# Strain.net
KiCad netlist of a schematic drawn in Altium Designer
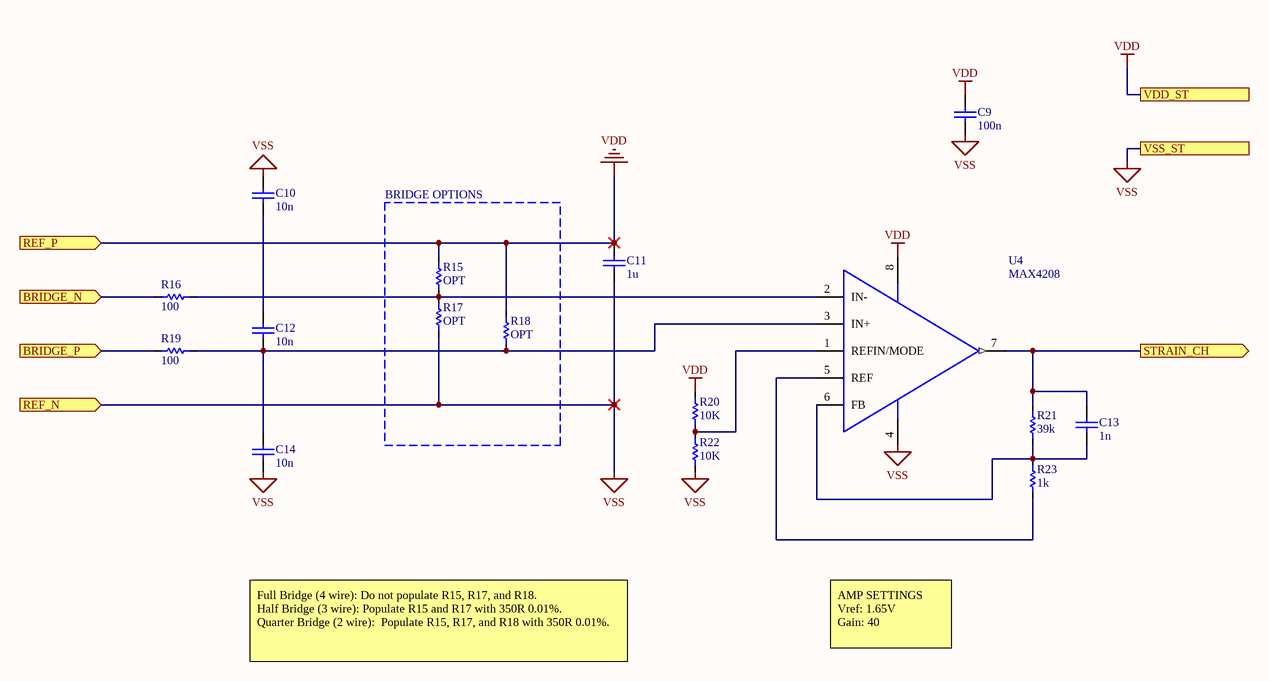
[diagram p0: Strain.SchDoc]

(export (version "E")
  (design (tool "Eeschema 10.0.6"))
  (components
    (comp (ref "C9")
      (value "100n")
      (footprint "CAP_0603_M")
      (description "CAP Cnom Vcap Ptol Dial 0603")
      (fields (field (name "CREATED BY") "JS"))
      (libsource (lib "Passives") (part "CAP_0603"))
    )
    (comp (ref "C10")
      (value "10n")
      (footprint "CAP_0603_M")
      (description "CAP Cnom Vcap Ptol Dial 0603")
      (fields (field (name "CREATED BY") "JS"))
      (libsource (lib "Passives") (part "CAP_0603"))
    )
    (comp (ref "C11")
      (value "1u")
      (footprint "CAP_0603_M")
      (description "CAP Cnom Vcap Ptol Dial 0603")
      (fields (field (name "CREATED BY") "JS"))
      (libsource (lib "Passives") (part "CAP_0603"))
    )
    (comp (ref "C12")
      (value "10n")
      (footprint "CAP_0603_M")
      (description "CAP Cnom Vcap Ptol Dial 0603")
      (fields (field (name "CREATED BY") "JS"))
      (libsource (lib "Passives") (part "CAP_0603"))
    )
    (comp (ref "C13")
      (value "1n")
      (footprint "CAP_0603_M")
      (description "CAP Cnom Vcap Ptol Dial 0603")
      (fields (field (name "CREATED BY") "JS"))
      (libsource (lib "Passives") (part "CAP_0603"))
    )
    (comp (ref "C14")
      (value "10n")
      (footprint "CAP_0603_M")
      (description "CAP Cnom Vcap Ptol Dial 0603")
      (fields (field (name "CREATED BY") "JS"))
      (libsource (lib "Passives") (part "CAP_0603"))
    )
    (comp (ref "R15")
      (value "OPT")
      (footprint "RES_0603_M")
      (description "RES OPT 1/5W 0603")
      (fields (field (name "CREATED BY") "JS"))
      (libsource (lib "Passives") (part "RES_0603"))
    )
    (comp (ref "R16")
      (value "100")
      (footprint "RES_0603_M")
      (description "RES OPT 1/5W 0603")
      (fields (field (name "CREATED BY") "JS"))
      (libsource (lib "Passives") (part "RES_0603"))
    )
    (comp (ref "R17")
      (value "OPT")
      (footprint "RES_0603_M")
      (description "RES OPT 1/5W 0603")
      (fields (field (name "CREATED BY") "JS"))
      (libsource (lib "Passives") (part "RES_0603"))
    )
    (comp (ref "R18")
      (value "OPT")
      (footprint "RES_0603_M")
      (description "RES OPT 1/5W 0603")
      (fields (field (name "CREATED BY") "JS"))
      (libsource (lib "Passives") (part "RES_0603"))
    )
    (comp (ref "R19")
      (value "100")
      (footprint "RES_0603_M")
      (description "RES OPT 1/5W 0603")
      (fields (field (name "CREATED BY") "JS"))
      (libsource (lib "Passives") (part "RES_0603"))
    )
    (comp (ref "R20")
      (value "10K")
      (footprint "RES_0603_M")
      (description "RES OPT 1/5W 0603")
      (fields (field (name "CREATED BY") "JS"))
      (libsource (lib "Passives") (part "RES_0603"))
    )
    (comp (ref "R21")
      (value "39k")
      (footprint "RES_0603_M")
      (description "RES OPT 1/5W 0603")
      (fields (field (name "CREATED BY") "JS"))
      (libsource (lib "Passives") (part "RES_0603"))
    )
    (comp (ref "R22")
      (value "10K")
      (footprint "RES_0603_M")
      (description "RES OPT 1/5W 0603")
      (fields (field (name "CREATED BY") "JS"))
      (libsource (lib "Passives") (part "RES_0603"))
    )
    (comp (ref "R23")
      (value "1k")
      (footprint "RES_0603_M")
      (description "RES OPT 1/5W 0603")
      (fields (field (name "CREATED BY") "JS"))
      (libsource (lib "Passives") (part "RES_0603"))
    )
    (comp (ref "U4")
      (value "MAX4208")
      (footprint "MAX4208_SOP127P600-8N")
      (fields (field (name "MANUFACTURER") "Maxim"))
      (libsource (lib "IC") (part "MAX4208"))
    )
  )
  (nets
    (net (code "1") (name "/BRIDGE_N") (class "Default")
      (node (ref "R16") (pin "1") (pinfunction "1_1") (pintype "passive"))
    )
    (net (code "2") (name "/BRIDGE_P") (class "Default")
      (node (ref "R19") (pin "1") (pinfunction "1_1") (pintype "passive"))
    )
    (net (code "3") (name "/STRAIN_CH") (class "Default")
      (node (ref "C13") (pin "2") (pinfunction "2_2") (pintype "passive"))
      (node (ref "R21") (pin "2") (pinfunction "2_2") (pintype "passive"))
      (node (ref "U4") (pin "7") (pinfunction "VO_7") (pintype "output"))
    )
    (net (code "4") (name "Net-(C10-Pad1)") (class "Default")
      (node (ref "C10") (pin "1") (pinfunction "1_1") (pintype "passive"))
      (node (ref "C12") (pin "2") (pinfunction "2_2") (pintype "passive"))
    )
    (net (code "5") (name "Net-(U4-FB)") (class "Default")
      (node (ref "C13") (pin "1") (pinfunction "1_1") (pintype "passive"))
      (node (ref "R21") (pin "1") (pinfunction "1_1") (pintype "passive"))
      (node (ref "R23") (pin "2") (pinfunction "2_2") (pintype "passive"))
      (node (ref "U4") (pin "6") (pinfunction "FB_6") (pintype "passive"))
    )
    (net (code "6") (name "Net-(U4-IN+)") (class "Default")
      (node (ref "C12") (pin "1") (pinfunction "1_1") (pintype "passive"))
      (node (ref "C14") (pin "2") (pinfunction "2_2") (pintype "passive"))
      (node (ref "R18") (pin "1") (pinfunction "1_1") (pintype "passive"))
      (node (ref "R19") (pin "2") (pinfunction "2_2") (pintype "passive"))
      (node (ref "U4") (pin "3") (pinfunction "IN+_3") (pintype "passive"))
    )
    (net (code "7") (name "Net-(U4-IN-)") (class "Default")
      (node (ref "R15") (pin "1") (pinfunction "1_1") (pintype "passive"))
      (node (ref "R16") (pin "2") (pinfunction "2_2") (pintype "passive"))
      (node (ref "R17") (pin "2") (pinfunction "2_2") (pintype "passive"))
      (node (ref "U4") (pin "2") (pinfunction "IN-_2") (pintype "passive"))
    )
    (net (code "8") (name "Net-(U4-REF)") (class "Default")
      (node (ref "R23") (pin "1") (pinfunction "1_1") (pintype "passive"))
      (node (ref "U4") (pin "5") (pinfunction "REF_5") (pintype "passive"))
    )
    (net (code "9") (name "Net-(U4-REFIN{slash}MODE)") (class "Default")
      (node (ref "R20") (pin "1") (pinfunction "1_1") (pintype "passive"))
      (node (ref "R22") (pin "2") (pinfunction "2_2") (pintype "passive"))
      (node (ref "U4") (pin "1") (pinfunction "REFIN/MODE_1") (pintype "passive"))
    )
    (net (code "10") (name "VDD") (class "Default")
      (node (ref "C11") (pin "2") (pinfunction "2_2") (pintype "passive"))
      (node (ref "C9") (pin "2") (pinfunction "2_2") (pintype "passive"))
      (node (ref "R15") (pin "2") (pinfunction "2_2") (pintype "passive"))
      (node (ref "R18") (pin "2") (pinfunction "2_2") (pintype "passive"))
      (node (ref "R20") (pin "2") (pinfunction "2_2") (pintype "passive"))
      (node (ref "U4") (pin "8") (pinfunction "V+_8") (pintype "power_in"))
    )
    (net (code "11") (name "VSS") (class "Default")
      (node (ref "C10") (pin "2") (pinfunction "2_2") (pintype "passive"))
      (node (ref "C11") (pin "1") (pinfunction "1_1") (pintype "passive"))
      (node (ref "C14") (pin "1") (pinfunction "1_1") (pintype "passive"))
      (node (ref "C9") (pin "1") (pinfunction "1_1") (pintype "passive"))
      (node (ref "R17") (pin "1") (pinfunction "1_1") (pintype "passive"))
      (node (ref "R22") (pin "1") (pinfunction "1_1") (pintype "passive"))
      (node (ref "U4") (pin "4") (pinfunction "V-_4") (pintype "power_in"))
    )
  )
)
